# FUZZFACEA.net
KiCad netlist of a schematic drawn in EAGLE
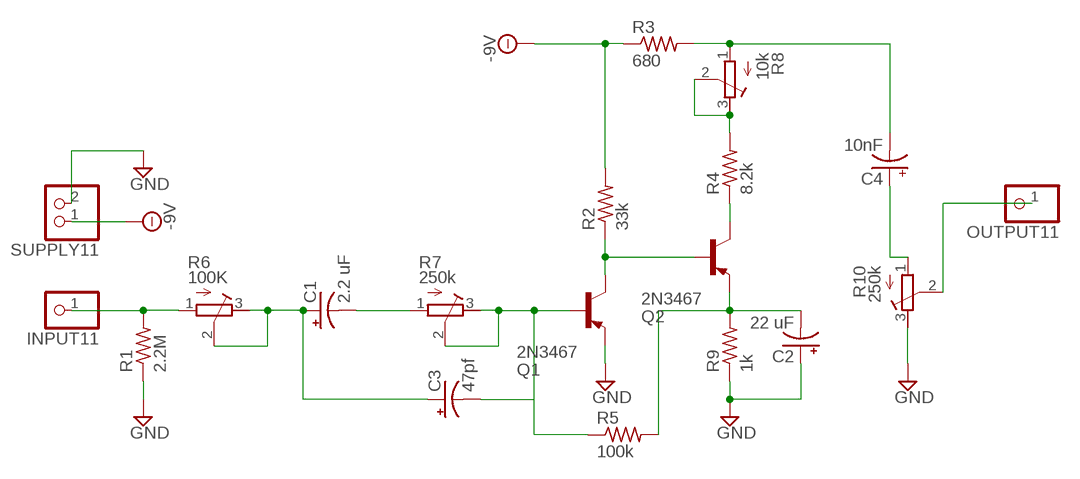
[diagram p0: schematic, sheet 1]

(export (version "E")
  (design (tool "Eeschema 10.0.6"))
  (components
    (comp (ref "C1")
      (value "2.2 uF")
      (footprint "eagle-import:TAP5-60")
      (libsource (lib "eagle-import") (part "CPOL-USTAP5-60"))
    )
    (comp (ref "C2")
      (value "22 uF")
      (footprint "eagle-import:TAP5-60")
      (libsource (lib "eagle-import") (part "CPOL-USTAP5-60"))
    )
    (comp (ref "C3")
      (value "47pf")
      (footprint "eagle-import:E2-4")
      (libsource (lib "eagle-import") (part "CPOL-USE2-4"))
    )
    (comp (ref "C4")
      (value "10nF")
      (footprint "eagle-import:E15-6")
      (libsource (lib "eagle-import") (part "CPOL-USE15-6AXIAL"))
    )
    (comp (ref "INPUT11")
      (value "PINHD-1X1")
      (footprint "eagle-import:1X01")
      (libsource (lib "eagle-import") (part "PINHD-1X1"))
    )
    (comp (ref "OUTPUT11")
      (value "PINHD-1X1")
      (footprint "eagle-import:1X01")
      (libsource (lib "eagle-import") (part "PINHD-1X1"))
    )
    (comp (ref "Q1")
      (value "2N3467")
      (footprint "eagle-import:TO39")
      (libsource (lib "eagle-import") (part "2N3467"))
    )
    (comp (ref "Q2")
      (value "2N3467")
      (footprint "eagle-import:TO39")
      (libsource (lib "eagle-import") (part "2N3467"))
    )
    (comp (ref "R1")
      (value "2.2M")
      (footprint "eagle-import:0411_12")
      (libsource (lib "eagle-import") (part "R-US_0411/12"))
    )
    (comp (ref "R2")
      (value "33k")
      (footprint "eagle-import:0411_12")
      (libsource (lib "eagle-import") (part "R-US_0411/12"))
    )
    (comp (ref "R3")
      (value "680")
      (footprint "eagle-import:0411_12")
      (libsource (lib "eagle-import") (part "R-US_0411/12"))
    )
    (comp (ref "R4")
      (value "8.2k")
      (footprint "eagle-import:0411_12")
      (libsource (lib "eagle-import") (part "R-US_0411/12"))
    )
    (comp (ref "R5")
      (value "100k")
      (footprint "eagle-import:0411_12")
      (libsource (lib "eagle-import") (part "R-US_0411/12"))
    )
    (comp (ref "R6")
      (value "100K")
      (footprint "eagle-import:RTRIM64X")
      (libsource (lib "eagle-import") (part "R-TRIMM64X"))
    )
    (comp (ref "R7")
      (value "250k")
      (footprint "eagle-import:RTRIM64X")
      (fields (field (name "SPICEPREFIX") "X"))
      (libsource (lib "eagle-import") (part "R-TRIMM64X"))
    )
    (comp (ref "R8")
      (value "10k")
      (footprint "eagle-import:RTRIM64X")
      (libsource (lib "eagle-import") (part "R-TRIMM64X"))
    )
    (comp (ref "R9")
      (value "1k")
      (footprint "eagle-import:0411_12")
      (libsource (lib "eagle-import") (part "R-US_0411/12"))
    )
    (comp (ref "R10")
      (value "250k")
      (footprint "eagle-import:RTRIM64X")
      (libsource (lib "eagle-import") (part "R-TRIMM64X"))
    )
    (comp (ref "SUPPLY11")
      (value "PINHD-1X2")
      (footprint "eagle-import:1X02")
      (libsource (lib "eagle-import") (part "PINHD-1X2"))
    )
  )
  (nets
    (net (code "1") (name "-9V") (class "Default")
      (node (ref "R2") (pin "2") (pinfunction "2_2") (pintype "passive"))
      (node (ref "R3") (pin "1") (pinfunction "1_1") (pintype "passive"))
      (node (ref "SUPPLY11") (pin "1") (pinfunction "1_1") (pintype "passive"))
    )
    (net (code "2") (name "GND") (class "Default")
      (node (ref "C2") (pin "+") (pinfunction "+_+") (pintype "passive"))
      (node (ref "Q1") (pin "1") (pinfunction "E_1") (pintype "passive"))
      (node (ref "R1") (pin "1") (pinfunction "1_1") (pintype "passive"))
      (node (ref "R10") (pin "3") (pinfunction "E_3") (pintype "passive"))
      (node (ref "R9") (pin "1") (pinfunction "1_1") (pintype "passive"))
      (node (ref "SUPPLY11") (pin "2") (pinfunction "2_2") (pintype "passive"))
    )
    (net (code "3") (name "Net-(Q1-B)") (class "Default")
      (node (ref "C3") (pin "-") (pinfunction "-_-") (pintype "passive"))
      (node (ref "Q1") (pin "2") (pinfunction "B_2") (pintype "passive"))
      (node (ref "R5") (pin "1") (pinfunction "1_1") (pintype "passive"))
      (node (ref "R7") (pin "2") (pinfunction "S_2") (pintype "passive"))
      (node (ref "R7") (pin "3") (pinfunction "E_3") (pintype "passive"))
    )
    (net (code "4") (name "Net-(Q1-C)") (class "Default")
      (node (ref "Q1") (pin "3") (pinfunction "C_3") (pintype "passive"))
      (node (ref "Q2") (pin "2") (pinfunction "B_2") (pintype "passive"))
      (node (ref "R2") (pin "1") (pinfunction "1_1") (pintype "passive"))
    )
    (net (code "5") (name "Net-(Q2-C)") (class "Default")
      (node (ref "Q2") (pin "3") (pinfunction "C_3") (pintype "passive"))
      (node (ref "R4") (pin "1") (pinfunction "1_1") (pintype "passive"))
    )
    (net (code "6") (name "Net-(Q2-E)") (class "Default")
      (node (ref "C2") (pin "-") (pinfunction "-_-") (pintype "passive"))
      (node (ref "Q2") (pin "1") (pinfunction "E_1") (pintype "passive"))
      (node (ref "R5") (pin "2") (pinfunction "2_2") (pintype "passive"))
      (node (ref "R9") (pin "2") (pinfunction "2_2") (pintype "passive"))
    )
    (net (code "7") (name "Net-(R6-A)") (class "Default")
      (node (ref "INPUT11") (pin "1") (pinfunction "1_1") (pintype "passive"))
      (node (ref "R1") (pin "2") (pinfunction "2_2") (pintype "passive"))
      (node (ref "R6") (pin "1") (pinfunction "A_1") (pintype "passive"))
    )
    (net (code "8") (name "Net-(R6-E)") (class "Default")
      (node (ref "C1") (pin "+") (pinfunction "+_+") (pintype "passive"))
      (node (ref "C3") (pin "+") (pinfunction "+_+") (pintype "passive"))
      (node (ref "R6") (pin "2") (pinfunction "S_2") (pintype "passive"))
      (node (ref "R6") (pin "3") (pinfunction "E_3") (pintype "passive"))
    )
    (net (code "9") (name "Net-(R7-A)") (class "Default")
      (node (ref "C1") (pin "-") (pinfunction "-_-") (pintype "passive"))
      (node (ref "R7") (pin "1") (pinfunction "A_1") (pintype "passive"))
    )
    (net (code "10") (name "Net-(R8-A)") (class "Default")
      (node (ref "C4") (pin "-") (pinfunction "-_-") (pintype "passive"))
      (node (ref "R3") (pin "2") (pinfunction "2_2") (pintype "passive"))
      (node (ref "R8") (pin "1") (pinfunction "A_1") (pintype "passive"))
    )
    (net (code "11") (name "Net-(R8-E)") (class "Default")
      (node (ref "R4") (pin "2") (pinfunction "2_2") (pintype "passive"))
      (node (ref "R8") (pin "2") (pinfunction "S_2") (pintype "passive"))
      (node (ref "R8") (pin "3") (pinfunction "E_3") (pintype "passive"))
    )
    (net (code "12") (name "Net-(R10-A)") (class "Default")
      (node (ref "C4") (pin "+") (pinfunction "+_+") (pintype "passive"))
      (node (ref "R10") (pin "1") (pinfunction "A_1") (pintype "passive"))
    )
    (net (code "13") (name "Net-(R10-S)") (class "Default")
      (node (ref "OUTPUT11") (pin "1") (pinfunction "1_1") (pintype "passive"))
      (node (ref "R10") (pin "2") (pinfunction "S_2") (pintype "passive"))
    )
  )
)
